# TelTail_Lights_EP_2v1.net
KiCad netlist of a schematic drawn in EAGLE
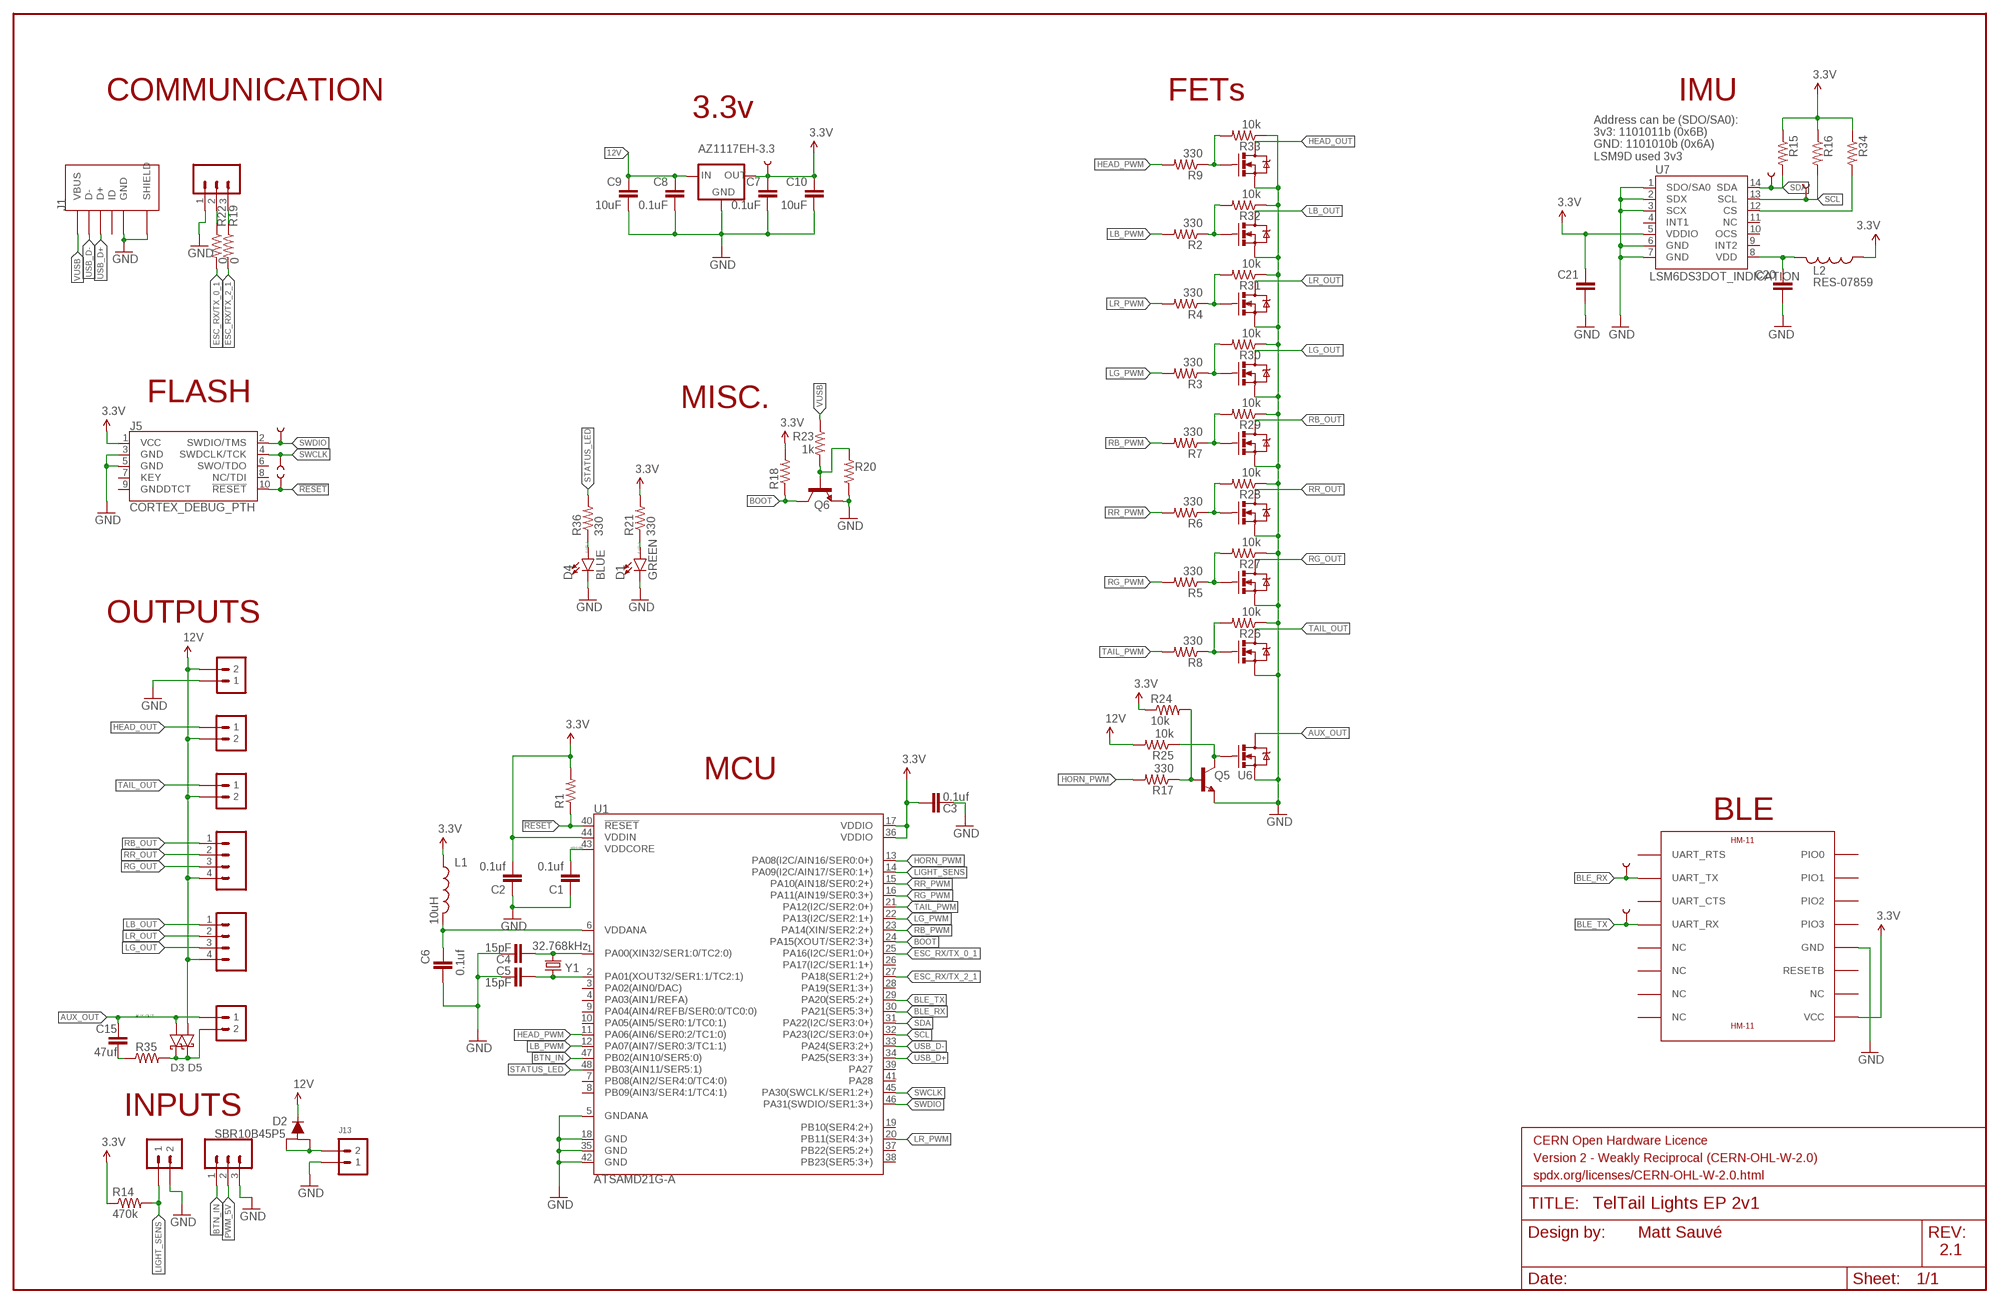
[diagram p0: schematic, sheet 1]

(export (version "E")
  (design (tool "Eeschema 10.0.6"))
  (components
    (comp (ref "C1")
      (value "0.1uf")
      (footprint "eagle-import:0603-CAP")
      (libsource (lib "eagle-import") (part "CAP0603-CAP"))
    )
    (comp (ref "C2")
      (value "0.1uf")
      (footprint "eagle-import:0603-CAP")
      (libsource (lib "eagle-import") (part "CAP0603-CAP"))
    )
    (comp (ref "C3")
      (value "0.1uf")
      (footprint "eagle-import:0603-CAP")
      (libsource (lib "eagle-import") (part "CAP0603-CAP"))
    )
    (comp (ref "C4")
      (value "15pF")
      (footprint "eagle-import:0603-CAP")
      (libsource (lib "eagle-import") (part "CAP0603-CAP"))
    )
    (comp (ref "C5")
      (value "15pF")
      (footprint "eagle-import:0603-CAP")
      (libsource (lib "eagle-import") (part "CAP0603-CAP"))
    )
    (comp (ref "C6")
      (value "0.1uf")
      (footprint "eagle-import:0603-CAP")
      (libsource (lib "eagle-import") (part "CAP0603-CAP"))
    )
    (comp (ref "C7")
      (value "0.1uF")
      (footprint "eagle-import:0603-CAP")
      (libsource (lib "eagle-import") (part "CAP0603-CAP"))
    )
    (comp (ref "C8")
      (value "0.1uF")
      (footprint "eagle-import:0603-CAP")
      (libsource (lib "eagle-import") (part "CAP0603-CAP"))
    )
    (comp (ref "C9")
      (value "10uF")
      (footprint "eagle-import:0603-CAP")
      (libsource (lib "eagle-import") (part "CAP0603-CAP"))
    )
    (comp (ref "C10")
      (value "10uF")
      (footprint "eagle-import:0603-CAP")
      (libsource (lib "eagle-import") (part "CAP0603-CAP"))
    )
    (comp (ref "C15")
      (value "47uf")
      (footprint "eagle-import:1210-CAP")
      (libsource (lib "eagle-import") (part "CAP1210"))
    )
    (comp (ref "C20")
      (value "0.1uF")
      (footprint "eagle-import:0603-CAP")
      (libsource (lib "eagle-import") (part "CAP0603-CAP"))
    )
    (comp (ref "C21")
      (value "0.1uF")
      (footprint "eagle-import:0603-CAP")
      (libsource (lib "eagle-import") (part "CAP0603-CAP"))
    )
    (comp (ref "D1")
      (value "GREEN")
      (footprint "eagle-import:LED-0603-2")
      (libsource (lib "eagle-import") (part "LED0603"))
    )
    (comp (ref "D2")
      (value "SBR10B45P5")
      (footprint "eagle-import:POWERDI5")
      (libsource (lib "eagle-import") (part "SBR10B45P5"))
    )
    (comp (ref "D3")
      (value "PMEG2010ER")
      (footprint "eagle-import:SOD-123W")
      (libsource (lib "eagle-import") (part "PMEG2010ER"))
    )
    (comp (ref "D4")
      (value "BLUE")
      (footprint "eagle-import:LED-0603-2")
      (libsource (lib "eagle-import") (part "LED0603"))
    )
    (comp (ref "D5")
      (value "PMEG2010ER")
      (footprint "eagle-import:SOD-123W")
      (libsource (lib "eagle-import") (part "PMEG2010ER"))
    )
    (comp (ref "FRAME1")
      (value "FRAME-LEDGER_CERN_WEAK")
      (footprint "eagle-import:CERN_WEAK")
      (libsource (lib "eagle-import") (part "FRAME-LEDGER_CERN_WEAK"))
    )
    (comp (ref "J1")
      (value "USB3160-XX-XXXX-X-X_REVA")
      (footprint "eagle-import:GCT_USB3160-XX-XXXX-X-X_REVA")
      (fields (field (name "MF") "Global Connector Technology") (field (name "MP") "USB3160-30-0170-0-C"))
      (libsource (lib "eagle-import") (part "USB3160-XX-XXXX-X-X_REVA"))
    )
    (comp (ref "J3")
      (value "JST_PH_3POS")
      (footprint "eagle-import:JST_PH_3POS")
      (libsource (lib "eagle-import") (part "JST_PH_3POS"))
    )
    (comp (ref "J4")
      (value "JST_PH_2POS")
      (footprint "eagle-import:JST_PH_2POS")
      (libsource (lib "eagle-import") (part "JST_PH_2POS"))
    )
    (comp (ref "J5")
      (value "CORTEX_DEBUG_PTH")
      (footprint "eagle-import:2X5-PTH-1.27MM-2")
      (libsource (lib "eagle-import") (part "CORTEX_DEBUG_PTH"))
    )
    (comp (ref "J6")
      (value "JST_PH_2POS")
      (footprint "eagle-import:JST_PH_2POS")
      (libsource (lib "eagle-import") (part "JST_PH_2POS"))
    )
    (comp (ref "J7")
      (value "JST_PH_2POS")
      (footprint "eagle-import:JST_PH_2POS")
      (libsource (lib "eagle-import") (part "JST_PH_2POS"))
    )
    (comp (ref "J8")
      (value "JST_PH_4POS")
      (footprint "eagle-import:JST_PH_4POS")
      (libsource (lib "eagle-import") (part "JST_PH_4POS"))
    )
    (comp (ref "J9")
      (value "JST_PH_4POS")
      (footprint "eagle-import:JST_PH_4POS")
      (libsource (lib "eagle-import") (part "JST_PH_4POS"))
    )
    (comp (ref "J10")
      (value "JST_PH_2POS")
      (footprint "eagle-import:JST_PH_2POS")
      (libsource (lib "eagle-import") (part "JST_PH_2POS"))
    )
    (comp (ref "J11")
      (value "JST_PH_2POS")
      (footprint "eagle-import:JST_PH_2POS")
      (libsource (lib "eagle-import") (part "JST_PH_2POS"))
    )
    (comp (ref "J12")
      (value "JST_PH_3POS")
      (footprint "eagle-import:JST_PH_3POS")
      (libsource (lib "eagle-import") (part "JST_PH_3POS"))
    )
    (comp (ref "J13")
      (value "TERM_BLOCK_SPRING_2POS_5MM")
      (footprint "eagle-import:TERM_BLOCK_SPRING_2POS_5MM")
      (libsource (lib "eagle-import") (part "TERM_BLOCK_SPRING_2POS_5MM"))
    )
    (comp (ref "L1")
      (value "10uH")
      (footprint "eagle-import:0603-IND")
      (libsource (lib "eagle-import") (part "INDUCTOR0603"))
    )
    (comp (ref "L2")
      (value "RES-07859")
      (footprint "eagle-import:0603-IND")
      (libsource (lib "eagle-import") (part "INDUCTOR0603"))
    )
    (comp (ref "Q1")
      (value "DUAL_NFET_3.5A")
      (footprint "eagle-import:TSOT26")
      (libsource (lib "eagle-import") (part "DUAL_NFET_3.5A"))
    )
    (comp (ref "Q2")
      (value "DUAL_NFET_3.5A")
      (footprint "eagle-import:TSOT26")
      (libsource (lib "eagle-import") (part "DUAL_NFET_3.5A"))
    )
    (comp (ref "Q3")
      (value "DUAL_NFET_3.5A")
      (footprint "eagle-import:TSOT26")
      (libsource (lib "eagle-import") (part "DUAL_NFET_3.5A"))
    )
    (comp (ref "Q4")
      (value "DUAL_NFET_3.5A")
      (footprint "eagle-import:TSOT26")
      (libsource (lib "eagle-import") (part "DUAL_NFET_3.5A"))
    )
    (comp (ref "Q5")
      (value "500mA/300V")
      (footprint "eagle-import:SOT23-3")
      (libsource (lib "eagle-import") (part "TRANS_NPN-MMBTA42"))
    )
    (comp (ref "Q6")
      (value "500mA/300V")
      (footprint "eagle-import:SOT23-3")
      (libsource (lib "eagle-import") (part "TRANS_NPN-MMBTA42"))
    )
    (comp (ref "R1")
      (value "10k")
      (footprint "eagle-import:RES-0402")
      (libsource (lib "eagle-import") (part "RES-0402"))
    )
    (comp (ref "R2")
      (value "330")
      (footprint "eagle-import:RES-0402")
      (libsource (lib "eagle-import") (part "RES-0402"))
    )
    (comp (ref "R3")
      (value "330")
      (footprint "eagle-import:RES-0402")
      (libsource (lib "eagle-import") (part "RES-0402"))
    )
    (comp (ref "R4")
      (value "330")
      (footprint "eagle-import:RES-0402")
      (libsource (lib "eagle-import") (part "RES-0402"))
    )
    (comp (ref "R5")
      (value "330")
      (footprint "eagle-import:RES-0402")
      (libsource (lib "eagle-import") (part "RES-0402"))
    )
    (comp (ref "R6")
      (value "330")
      (footprint "eagle-import:RES-0402")
      (libsource (lib "eagle-import") (part "RES-0402"))
    )
    (comp (ref "R7")
      (value "330")
      (footprint "eagle-import:RES-0402")
      (libsource (lib "eagle-import") (part "RES-0402"))
    )
    (comp (ref "R8")
      (value "330")
      (footprint "eagle-import:RES-0402")
      (libsource (lib "eagle-import") (part "RES-0402"))
    )
    (comp (ref "R9")
      (value "330")
      (footprint "eagle-import:RES-0402")
      (libsource (lib "eagle-import") (part "RES-0402"))
    )
    (comp (ref "R14")
      (value "470k")
      (footprint "eagle-import:RES-0603")
      (libsource (lib "eagle-import") (part "RES-0603"))
    )
    (comp (ref "R15")
      (value "10k")
      (footprint "eagle-import:RES-0402")
      (libsource (lib "eagle-import") (part "RES-0402"))
    )
    (comp (ref "R16")
      (value "10k")
      (footprint "eagle-import:RES-0402")
      (libsource (lib "eagle-import") (part "RES-0402"))
    )
    (comp (ref "R17")
      (value "330")
      (footprint "eagle-import:RES-0402")
      (libsource (lib "eagle-import") (part "RES-0402"))
    )
    (comp (ref "R18")
      (value "10k")
      (footprint "eagle-import:RES-0402")
      (libsource (lib "eagle-import") (part "RES-0402"))
    )
    (comp (ref "R19")
      (value "0")
      (footprint "eagle-import:RES-0603")
      (libsource (lib "eagle-import") (part "RES-0603"))
    )
    (comp (ref "R20")
      (value "10k")
      (footprint "eagle-import:RES-0402")
      (libsource (lib "eagle-import") (part "RES-0402"))
    )
    (comp (ref "R21")
      (value "330")
      (footprint "eagle-import:RES-0402")
      (libsource (lib "eagle-import") (part "RES-0402"))
    )
    (comp (ref "R22")
      (value "0")
      (footprint "eagle-import:RES-0603")
      (libsource (lib "eagle-import") (part "RES-0603"))
    )
    (comp (ref "R23")
      (value "1k")
      (footprint "eagle-import:RES-0402")
      (libsource (lib "eagle-import") (part "RES-0402"))
    )
    (comp (ref "R24")
      (value "10k")
      (footprint "eagle-import:RES-0402")
      (libsource (lib "eagle-import") (part "RES-0402"))
    )
    (comp (ref "R25")
      (value "10k")
      (footprint "eagle-import:RES-0402")
      (libsource (lib "eagle-import") (part "RES-0402"))
    )
    (comp (ref "R26")
      (value "10k")
      (footprint "eagle-import:RES-0402")
      (libsource (lib "eagle-import") (part "RES-0402"))
    )
    (comp (ref "R27")
      (value "10k")
      (footprint "eagle-import:RES-0402")
      (libsource (lib "eagle-import") (part "RES-0402"))
    )
    (comp (ref "R28")
      (value "10k")
      (footprint "eagle-import:RES-0402")
      (libsource (lib "eagle-import") (part "RES-0402"))
    )
    (comp (ref "R29")
      (value "10k")
      (footprint "eagle-import:RES-0402")
      (libsource (lib "eagle-import") (part "RES-0402"))
    )
    (comp (ref "R30")
      (value "10k")
      (footprint "eagle-import:RES-0402")
      (libsource (lib "eagle-import") (part "RES-0402"))
    )
    (comp (ref "R31")
      (value "10k")
      (footprint "eagle-import:RES-0402")
      (libsource (lib "eagle-import") (part "RES-0402"))
    )
    (comp (ref "R32")
      (value "10k")
      (footprint "eagle-import:RES-0402")
      (libsource (lib "eagle-import") (part "RES-0402"))
    )
    (comp (ref "R33")
      (value "10k")
      (footprint "eagle-import:RES-0402")
      (libsource (lib "eagle-import") (part "RES-0402"))
    )
    (comp (ref "R34")
      (value "10k")
      (footprint "eagle-import:RES-0402")
      (libsource (lib "eagle-import") (part "RES-0402"))
    )
    (comp (ref "R35")
      (value "100")
      (footprint "eagle-import:0805-RES")
      (libsource (lib "eagle-import") (part "RESISTOR0805"))
    )
    (comp (ref "R36")
      (value "330")
      (footprint "eagle-import:RES-0402")
      (libsource (lib "eagle-import") (part "RES-0402"))
    )
    (comp (ref "TP1")
      (value "1MM_TP")
      (footprint "eagle-import:1MM_TP")
      (libsource (lib "eagle-import") (part "1MM_TP"))
    )
    (comp (ref "TP2")
      (value "1MM_TP")
      (footprint "eagle-import:1MM_TP")
      (libsource (lib "eagle-import") (part "1MM_TP"))
    )
    (comp (ref "TP3")
      (value "1MM_TP")
      (footprint "eagle-import:1MM_TP")
      (libsource (lib "eagle-import") (part "1MM_TP"))
    )
    (comp (ref "TP4")
      (value "1MM_TP")
      (footprint "eagle-import:1MM_TP")
      (libsource (lib "eagle-import") (part "1MM_TP"))
    )
    (comp (ref "TP5")
      (value "1MM_TP")
      (footprint "eagle-import:1MM_TP")
      (libsource (lib "eagle-import") (part "1MM_TP"))
    )
    (comp (ref "TP8")
      (value "1MM_TP")
      (footprint "eagle-import:1MM_TP")
      (libsource (lib "eagle-import") (part "1MM_TP"))
    )
    (comp (ref "TP9")
      (value "1MM_TP")
      (footprint "eagle-import:1MM_TP")
      (libsource (lib "eagle-import") (part "1MM_TP"))
    )
    (comp (ref "TP10")
      (value "1MM_TP")
      (footprint "eagle-import:1MM_TP")
      (libsource (lib "eagle-import") (part "1MM_TP"))
    )
    (comp (ref "U1")
      (value "ATSAMD21G-A")
      (footprint "eagle-import:TQFP-48")
      (libsource (lib "eagle-import") (part "ATSAMD21G-A"))
    )
    (comp (ref "U3")
      (value "HM-11")
      (footprint "eagle-import:HM-11")
      (libsource (lib "eagle-import") (part "HM-11"))
    )
    (comp (ref "U4")
      (value "AZ1117EH-3.3")
      (footprint "eagle-import:SOT-223")
      (libsource (lib "eagle-import") (part "AZ1117EH-3.3"))
    )
    (comp (ref "U6")
      (value "PSMN8R5-60YS")
      (footprint "eagle-import:SOT669")
      (libsource (lib "eagle-import") (part "PSMN8R5-60YS"))
    )
    (comp (ref "U7")
      (value "LSM6DS3DOT_INDICATION")
      (footprint "eagle-import:LGA14L_DOT_INDICATOR")
      (libsource (lib "eagle-import") (part "LSM6DS3DOT_INDICATION"))
    )
    (comp (ref "Y1")
      (value "32.768kHz")
      (footprint "eagle-import:CRYSTAL-SMD-3.2X1.5MM")
      (libsource (lib "eagle-import") (part "CRYSTAL-32.768KHZSMD-3.2X1.5"))
    )
  )
  (nets
    (net (code "1") (name "/P_LED_0") (class "Default")
      (node (ref "D1") (pin "A") (pinfunction "A_A") (pintype "passive"))
      (node (ref "R21") (pin "1") (pinfunction "1_1") (pintype "passive"))
    )
    (net (code "2") (name "/S_LED_0") (class "Default")
      (node (ref "D4") (pin "A") (pinfunction "A_A") (pintype "passive"))
      (node (ref "R36") (pin "1") (pinfunction "1_1") (pintype "passive"))
    )
    (net (code "3") (name "/VDDCORE") (class "Default")
      (node (ref "C1") (pin "2") (pinfunction "2_2") (pintype "passive"))
      (node (ref "U1") (pin "43") (pinfunction "VDDCORE_43") (pintype "bidirectional"))
    )
    (net (code "4") (name "/~{RESET}") (class "Default")
      (node (ref "J5") (pin "10") (pinfunction "~{RESET}_10") (pintype "bidirectional"))
      (node (ref "R1") (pin "1") (pinfunction "1_1") (pintype "passive"))
      (node (ref "TP10") (pin "P$1") (pinfunction "1_P$1") (pintype "bidirectional"))
      (node (ref "U1") (pin "40") (pinfunction "~{RESET}_40") (pintype "bidirectional"))
    )
    (net (code "5") (name "3.3V") (class "Default")
      (node (ref "C10") (pin "1") (pinfunction "1_1") (pintype "passive"))
      (node (ref "C2") (pin "2") (pinfunction "2_2") (pintype "passive"))
      (node (ref "C21") (pin "1") (pinfunction "1_1") (pintype "passive"))
      (node (ref "C3") (pin "2") (pinfunction "2_2") (pintype "passive"))
      (node (ref "C7") (pin "1") (pinfunction "1_1") (pintype "passive"))
      (node (ref "J5") (pin "1") (pinfunction "VCC_1") (pintype "bidirectional"))
      (node (ref "L1") (pin "1") (pinfunction "1_1") (pintype "passive"))
      (node (ref "L2") (pin "1") (pinfunction "1_1") (pintype "passive"))
      (node (ref "R1") (pin "2") (pinfunction "2_2") (pintype "passive"))
      (node (ref "R14") (pin "1") (pinfunction "1_1") (pintype "passive"))
      (node (ref "R15") (pin "1") (pinfunction "1_1") (pintype "passive"))
      (node (ref "R16") (pin "1") (pinfunction "1_1") (pintype "passive"))
      (node (ref "R18") (pin "2") (pinfunction "2_2") (pintype "passive"))
      (node (ref "R21") (pin "2") (pinfunction "2_2") (pintype "passive"))
      (node (ref "R24") (pin "1") (pinfunction "1_1") (pintype "passive"))
      (node (ref "R34") (pin "1") (pinfunction "1_1") (pintype "passive"))
      (node (ref "TP3") (pin "P$1") (pinfunction "1_P$1") (pintype "bidirectional"))
      (node (ref "U1") (pin "17") (pinfunction "VDDIO_17") (pintype "bidirectional"))
      (node (ref "U1") (pin "36") (pinfunction "VDDIO_36") (pintype "bidirectional"))
      (node (ref "U1") (pin "44") (pinfunction "VDDIN_44") (pintype "bidirectional"))
      (node (ref "U3") (pin "VCC") (pinfunction "VCC_VCC") (pintype "bidirectional"))
      (node (ref "U4") (pin "2") (pinfunction "OUT_2") (pintype "passive"))
      (node (ref "U4") (pin "4") (pinfunction "OUT_4") (pintype "passive"))
      (node (ref "U7") (pin "5") (pinfunction "VDDIO_5") (pintype "bidirectional"))
    )
    (net (code "6") (name "12V") (class "Default")
      (node (ref "C8") (pin "1") (pinfunction "1_1") (pintype "passive"))
      (node (ref "C9") (pin "1") (pinfunction "1_1") (pintype "passive"))
      (node (ref "D2") (pin "CATHODE") (pinfunction "C_CATHODE") (pintype "passive"))
      (node (ref "D5") (pin "2") (pinfunction "ANODE_2") (pintype "bidirectional"))
      (node (ref "J4") (pin "2") (pinfunction "2_2") (pintype "passive"))
      (node (ref "J6") (pin "2") (pinfunction "2_2") (pintype "passive"))
      (node (ref "J7") (pin "2") (pinfunction "2_2") (pintype "passive"))
      (node (ref "J8") (pin "4") (pinfunction "4_4") (pintype "passive"))
      (node (ref "J9") (pin "4") (pinfunction "4_4") (pintype "passive"))
      (node (ref "R25") (pin "2") (pinfunction "2_2") (pintype "passive"))
      (node (ref "U4") (pin "3") (pinfunction "IN_3") (pintype "input"))
    )
    (net (code "7") (name "AUX_OUT") (class "Default")
      (node (ref "C15") (pin "1") (pinfunction "1_1") (pintype "passive"))
      (node (ref "D3") (pin "2") (pinfunction "ANODE_2") (pintype "bidirectional"))
      (node (ref "J10") (pin "1") (pinfunction "1_1") (pintype "passive"))
      (node (ref "U6") (pin "P$1") (pinfunction "D_P$1") (pintype "passive"))
      (node (ref "U6") (pin "P$2") (pinfunction "D_P$2") (pintype "passive"))
    )
    (net (code "8") (name "BLE_RX") (class "Default")
      (node (ref "TP2") (pin "P$1") (pinfunction "1_P$1") (pintype "bidirectional"))
      (node (ref "U1") (pin "30") (pinfunction "PA21(SER5:3+)_30") (pintype "bidirectional"))
      (node (ref "U3") (pin "UART_TX") (pinfunction "UART_TX_UART_TX") (pintype "bidirectional"))
    )
    (net (code "9") (name "BLE_TX") (class "Default")
      (node (ref "TP1") (pin "P$1") (pinfunction "1_P$1") (pintype "bidirectional"))
      (node (ref "U1") (pin "29") (pinfunction "PA20(SER5:2+)_29") (pintype "bidirectional"))
      (node (ref "U3") (pin "UART_RX") (pinfunction "UART_RX_UART_RX") (pintype "bidirectional"))
    )
    (net (code "10") (name "BOOT") (class "Default")
      (node (ref "Q6") (pin "3") (pinfunction "C_3") (pintype "passive"))
      (node (ref "R18") (pin "1") (pinfunction "1_1") (pintype "passive"))
      (node (ref "U1") (pin "24") (pinfunction "PA15(XOUT/SER2:3+)_24") (pintype "bidirectional"))
    )
    (net (code "11") (name "BTN_IN") (class "Default")
      (node (ref "J12") (pin "1") (pinfunction "2_1") (pintype "passive"))
      (node (ref "U1") (pin "47") (pinfunction "PB02(AIN10/SER5:0)_47") (pintype "bidirectional"))
    )
    (net (code "12") (name "ESC_RX{slash}TX_0_1") (class "Default")
      (node (ref "R22") (pin "2") (pinfunction "2_2") (pintype "passive"))
      (node (ref "U1") (pin "25") (pinfunction "PA16(I2C/SER1:0+)_25") (pintype "bidirectional"))
    )
    (net (code "13") (name "ESC_RX{slash}TX_2_1") (class "Default")
      (node (ref "R19") (pin "2") (pinfunction "2_2") (pintype "passive"))
      (node (ref "U1") (pin "27") (pinfunction "PA18(SER1:2+)_27") (pintype "bidirectional"))
    )
    (net (code "14") (name "GND") (class "Default")
      (node (ref "C1") (pin "1") (pinfunction "1_1") (pintype "passive"))
      (node (ref "C10") (pin "2") (pinfunction "2_2") (pintype "passive"))
      (node (ref "C2") (pin "1") (pinfunction "1_1") (pintype "passive"))
      (node (ref "C20") (pin "2") (pinfunction "2_2") (pintype "passive"))
      (node (ref "C21") (pin "2") (pinfunction "2_2") (pintype "passive"))
      (node (ref "C3") (pin "1") (pinfunction "1_1") (pintype "passive"))
      (node (ref "C4") (pin "2") (pinfunction "2_2") (pintype "passive"))
      (node (ref "C5") (pin "2") (pinfunction "2_2") (pintype "passive"))
      (node (ref "C6") (pin "2") (pinfunction "2_2") (pintype "passive"))
      (node (ref "C7") (pin "2") (pinfunction "2_2") (pintype "passive"))
      (node (ref "C8") (pin "2") (pinfunction "2_2") (pintype "passive"))
      (node (ref "C9") (pin "2") (pinfunction "2_2") (pintype "passive"))
      (node (ref "D1") (pin "C") (pinfunction "C_C") (pintype "passive"))
      (node (ref "D4") (pin "C") (pinfunction "C_C") (pintype "passive"))
      (node (ref "J1") (pin "5") (pinfunction "GND_5") (pintype "power_in"))
      (node (ref "J1") (pin "6") (pinfunction "SHIELD_6") (pintype "passive"))
      (node (ref "J1") (pin "7") (pinfunction "SHIELD_7") (pintype "passive"))
      (node (ref "J1") (pin "8") (pinfunction "SHIELD_8") (pintype "passive"))
      (node (ref "J11") (pin "2") (pinfunction "2_2") (pintype "passive"))
      (node (ref "J12") (pin "3") (pinfunction "4_3") (pintype "passive"))
      (node (ref "J13") (pin "P1_1") (pinfunction "1_P1_1") (pintype "passive"))
      (node (ref "J13") (pin "P1_2") (pinfunction "1_P1_2") (pintype "passive"))
      (node (ref "J3") (pin "1") (pinfunction "2_1") (pintype "passive"))
      (node (ref "J4") (pin "1") (pinfunction "1_1") (pintype "passive"))
      (node (ref "J5") (pin "3") (pinfunction "GND_3") (pintype "bidirectional"))
      (node (ref "J5") (pin "5") (pinfunction "GND_5") (pintype "bidirectional"))
      (node (ref "Q1") (pin "2") (pinfunction "S_2") (pintype "passive"))
      (node (ref "Q1") (pin "5") (pinfunction "S_5") (pintype "passive"))
      (node (ref "Q2") (pin "2") (pinfunction "S_2") (pintype "passive"))
      (node (ref "Q2") (pin "5") (pinfunction "S_5") (pintype "passive"))
      (node (ref "Q3") (pin "2") (pinfunction "S_2") (pintype "passive"))
      (node (ref "Q3") (pin "5") (pinfunction "S_5") (pintype "passive"))
      (node (ref "Q4") (pin "2") (pinfunction "S_2") (pintype "passive"))
      (node (ref "Q4") (pin "5") (pinfunction "S_5") (pintype "passive"))
      (node (ref "Q5") (pin "2") (pinfunction "E_2") (pintype "passive"))
      (node (ref "Q6") (pin "2") (pinfunction "E_2") (pintype "passive"))
      (node (ref "R20") (pin "1") (pinfunction "1_1") (pintype "passive"))
      (node (ref "R26") (pin "1") (pinfunction "1_1") (pintype "passive"))
      (node (ref "R27") (pin "1") (pinfunction "1_1") (pintype "passive"))
      (node (ref "R28") (pin "1") (pinfunction "1_1") (pintype "passive"))
      (node (ref "R29") (pin "1") (pinfunction "1_1") (pintype "passive"))
      (node (ref "R30") (pin "1") (pinfunction "1_1") (pintype "passive"))
      (node (ref "R31") (pin "1") (pinfunction "1_1") (pintype "passive"))
      (node (ref "R32") (pin "1") (pinfunction "1_1") (pintype "passive"))
      (node (ref "R33") (pin "1") (pinfunction "1_1") (pintype "passive"))
      (node (ref "U1") (pin "18") (pinfunction "GND_18") (pintype "bidirectional"))
      (node (ref "U1") (pin "35") (pinfunction "GND_35") (pintype "bidirectional"))
      (node (ref "U1") (pin "42") (pinfunction "GND_42") (pintype "bidirectional"))
      (node (ref "U1") (pin "5") (pinfunction "GNDANA_5") (pintype "bidirectional"))
      (node (ref "U3") (pin "GND") (pinfunction "GND_GND") (pintype "bidirectional"))
      (node (ref "U4") (pin "1") (pinfunction "GND_1") (pintype "input"))
      (node (ref "U6") (pin "1") (pinfunction "S_1") (pintype "passive"))
      (node (ref "U6") (pin "2") (pinfunction "S_2") (pintype "passive"))
      (node (ref "U6") (pin "3") (pinfunction "S_3") (pintype "passive"))
      (node (ref "U7") (pin "1") (pinfunction "SDO/SA0_1") (pintype "bidirectional"))
      (node (ref "U7") (pin "2") (pinfunction "SDX_2") (pintype "bidirectional"))
      (node (ref "U7") (pin "3") (pinfunction "SCX_3") (pintype "bidirectional"))
      (node (ref "U7") (pin "6") (pinfunction "GND_6") (pintype "bidirectional"))
      (node (ref "U7") (pin "7") (pinfunction "GND_7") (pintype "bidirectional"))
    )
    (net (code "15") (name "HEAD_OUT") (class "Default")
      (node (ref "J6") (pin "1") (pinfunction "1_1") (pintype "passive"))
      (node (ref "Q1") (pin "4") (pinfunction "D_4") (pintype "passive"))
    )
    (net (code "16") (name "HEAD_PWM") (class "Default")
      (node (ref "R9") (pin "2") (pinfunction "2_2") (pintype "passive"))
      (node (ref "U1") (pin "11") (pinfunction "PA06(AIN6/SER0:2/TC1:0)_11") (pintype "bidirectional"))
    )
    (net (code "17") (name "HORN_PWM") (class "Default")
      (node (ref "R17") (pin "2") (pinfunction "2_2") (pintype "passive"))
      (node (ref "U1") (pin "13") (pinfunction "PA08(I2C/AIN16/SER0:0+)_13") (pintype "bidirectional"))
    )
    (net (code "18") (name "LB_OUT") (class "Default")
      (node (ref "J9") (pin "1") (pinfunction "1_1") (pintype "passive"))
      (node (ref "Q1") (pin "6") (pinfunction "D_6") (pintype "passive"))
    )
    (net (code "19") (name "LB_PWM") (class "Default")
      (node (ref "R2") (pin "2") (pinfunction "2_2") (pintype "passive"))
      (node (ref "U1") (pin "12") (pinfunction "PA07(AIN7/SER0:3/TC1:1)_12") (pintype "bidirectional"))
    )
    (net (code "20") (name "LG_OUT") (class "Default")
      (node (ref "J9") (pin "3") (pinfunction "3_3") (pintype "passive"))
      (node (ref "Q2") (pin "6") (pinfunction "D_6") (pintype "passive"))
    )
    (net (code "21") (name "LG_PWM") (class "Default")
      (node (ref "R3") (pin "2") (pinfunction "2_2") (pintype "passive"))
      (node (ref "U1") (pin "22") (pinfunction "PA13(I2C/SER2:1+)_22") (pintype "bidirectional"))
    )
    (net (code "22") (name "LIGHT_SENS") (class "Default")
      (node (ref "J11") (pin "1") (pinfunction "1_1") (pintype "passive"))
      (node (ref "R14") (pin "2") (pinfunction "2_2") (pintype "passive"))
      (node (ref "U1") (pin "14") (pinfunction "PA09(I2C/AIN17/SER0:1+)_14") (pintype "bidirectional"))
    )
    (net (code "23") (name "LR_OUT") (class "Default")
      (node (ref "J9") (pin "2") (pinfunction "2_2") (pintype "passive"))
      (node (ref "Q2") (pin "4") (pinfunction "D_4") (pintype "passive"))
    )
    (net (code "24") (name "LR_PWM") (class "Default")
      (node (ref "R4") (pin "2") (pinfunction "2_2") (pintype "passive"))
      (node (ref "U1") (pin "20") (pinfunction "PB11(SER4:3+)_20") (pintype "bidirectional"))
    )
    (net (code "25") (name "Net-(C15-Pad2)") (class "Default")
      (node (ref "C15") (pin "2") (pinfunction "2_2") (pintype "passive"))
      (node (ref "R35") (pin "1") (pinfunction "1_1") (pintype "passive"))
    )
    (net (code "26") (name "Net-(D2-A)") (class "Default")
      (node (ref "D2") (pin "ANODE1") (pinfunction "A_ANODE1") (pintype "passive"))
      (node (ref "D2") (pin "ANODE2") (pinfunction "A1_ANODE2") (pintype "passive"))
      (node (ref "J13") (pin "P2_1") (pinfunction "2_P2_1") (pintype "passive"))
      (node (ref "J13") (pin "P2_2") (pinfunction "2_P2_2") (pintype "passive"))
    )
    (net (code "27") (name "Net-(D3-CATHODE)") (class "Default")
      (node (ref "D3") (pin "1") (pinfunction "CATHODE_1") (pintype "bidirectional"))
      (node (ref "D5") (pin "1") (pinfunction "CATHODE_1") (pintype "bidirectional"))
      (node (ref "J10") (pin "2") (pinfunction "2_2") (pintype "passive"))
      (node (ref "R35") (pin "2") (pinfunction "2_2") (pintype "passive"))
    )
    (net (code "28") (name "Net-(J3-3)") (class "Default")
      (node (ref "J3") (pin "2") (pinfunction "3_2") (pintype "passive"))
      (node (ref "R22") (pin "1") (pinfunction "1_1") (pintype "passive"))
    )
    (net (code "29") (name "Net-(J3-4)") (class "Default")
      (node (ref "J3") (pin "3") (pinfunction "4_3") (pintype "passive"))
      (node (ref "R19") (pin "1") (pinfunction "1_1") (pintype "passive"))
    )
    (net (code "30") (name "Net-(Q1A-G)") (class "Default")
      (node (ref "Q1") (pin "1") (pinfunction "G_1") (pintype "passive"))
      (node (ref "R2") (pin "1") (pinfunction "1_1") (pintype "passive"))
      (node (ref "R32") (pin "2") (pinfunction "2_2") (pintype "passive"))
    )
    (net (code "31") (name "Net-(Q1B-G)") (class "Default")
      (node (ref "Q1") (pin "3") (pinfunction "G_3") (pintype "passive"))
      (node (ref "R33") (pin "2") (pinfunction "2_2") (pintype "passive"))
      (node (ref "R9") (pin "1") (pinfunction "1_1") (pintype "passive"))
    )
    (net (code "32") (name "Net-(Q2A-G)") (class "Default")
      (node (ref "Q2") (pin "1") (pinfunction "G_1") (pintype "passive"))
      (node (ref "R3") (pin "1") (pinfunction "1_1") (pintype "passive"))
      (node (ref "R30") (pin "2") (pinfunction "2_2") (pintype "passive"))
    )
    (net (code "33") (name "Net-(Q2B-G)") (class "Default")
      (node (ref "Q2") (pin "3") (pinfunction "G_3") (pintype "passive"))
      (node (ref "R31") (pin "2") (pinfunction "2_2") (pintype "passive"))
      (node (ref "R4") (pin "1") (pinfunction "1_1") (pintype "passive"))
    )
    (net (code "34") (name "Net-(Q3A-G)") (class "Default")
      (node (ref "Q3") (pin "1") (pinfunction "G_1") (pintype "passive"))
      (node (ref "R28") (pin "2") (pinfunction "2_2") (pintype "passive"))
      (node (ref "R6") (pin "1") (pinfunction "1_1") (pintype "passive"))
    )
    (net (code "35") (name "Net-(Q3B-G)") (class "Default")
      (node (ref "Q3") (pin "3") (pinfunction "G_3") (pintype "passive"))
      (node (ref "R29") (pin "2") (pinfunction "2_2") (pintype "passive"))
      (node (ref "R7") (pin "1") (pinfunction "1_1") (pintype "passive"))
    )
    (net (code "36") (name "Net-(Q4A-G)") (class "Default")
      (node (ref "Q4") (pin "1") (pinfunction "G_1") (pintype "passive"))
      (node (ref "R26") (pin "2") (pinfunction "2_2") (pintype "passive"))
      (node (ref "R8") (pin "1") (pinfunction "1_1") (pintype "passive"))
    )
    (net (code "37") (name "Net-(Q4B-G)") (class "Default")
      (node (ref "Q4") (pin "3") (pinfunction "G_3") (pintype "passive"))
      (node (ref "R27") (pin "2") (pinfunction "2_2") (pintype "passive"))
      (node (ref "R5") (pin "1") (pinfunction "1_1") (pintype "passive"))
    )
    (net (code "38") (name "Net-(Q5-B)") (class "Default")
      (node (ref "Q5") (pin "1") (pinfunction "B_1") (pintype "passive"))
      (node (ref "R17") (pin "1") (pinfunction "1_1") (pintype "passive"))
      (node (ref "R24") (pin "2") (pinfunction "2_2") (pintype "passive"))
    )
    (net (code "39") (name "Net-(Q5-C)") (class "Default")
      (node (ref "Q5") (pin "3") (pinfunction "C_3") (pintype "passive"))
      (node (ref "R25") (pin "1") (pinfunction "1_1") (pintype "passive"))
      (node (ref "U6") (pin "4") (pinfunction "G_4") (pintype "passive"))
    )
    (net (code "40") (name "Net-(Q6-B)") (class "Default")
      (node (ref "Q6") (pin "1") (pinfunction "B_1") (pintype "passive"))
      (node (ref "R20") (pin "2") (pinfunction "2_2") (pintype "passive"))
      (node (ref "R23") (pin "2") (pinfunction "2_2") (pintype "passive"))
    )
    (net (code "41") (name "Net-(U1-PA00(XIN32{slash}SER1:0{slash}TC2:0))") (class "Default")
      (node (ref "C4") (pin "1") (pinfunction "1_1") (pintype "passive"))
      (node (ref "U1") (pin "1") (pinfunction "PA00(XIN32/SER1:0/TC2:0)_1") (pintype "bidirectional"))
      (node (ref "Y1") (pin "P$2") (pinfunction "2_P$2") (pintype "passive"))
    )
    (net (code "42") (name "Net-(U1-PA01(XOUT32{slash}SER1:1{slash}TC2:1))") (class "Default")
      (node (ref "C5") (pin "1") (pinfunction "1_1") (pintype "passive"))
      (node (ref "U1") (pin "2") (pinfunction "PA01(XOUT32/SER1:1/TC2:1)_2") (pintype "bidirectional"))
      (node (ref "Y1") (pin "P$1") (pinfunction "1_P$1") (pintype "passive"))
    )
    (net (code "43") (name "Net-(U1-VDDANA)") (class "Default")
      (node (ref "C6") (pin "1") (pinfunction "1_1") (pintype "passive"))
      (node (ref "L1") (pin "2") (pinfunction "2_2") (pintype "passive"))
      (node (ref "U1") (pin "6") (pinfunction "VDDANA_6") (pintype "bidirectional"))
    )
    (net (code "44") (name "Net-(U7-CS)") (class "Default")
      (node (ref "R34") (pin "2") (pinfunction "2_2") (pintype "passive"))
      (node (ref "U7") (pin "12") (pinfunction "CS_12") (pintype "bidirectional"))
    )
    (net (code "45") (name "Net-(U7-VDD)") (class "Default")
      (node (ref "C20") (pin "1") (pinfunction "1_1") (pintype "passive"))
      (node (ref "L2") (pin "2") (pinfunction "2_2") (pintype "passive"))
      (node (ref "U7") (pin "8") (pinfunction "VDD_8") (pintype "bidirectional"))
    )
    (net (code "46") (name "PWM_5V") (class "Default")
      (node (ref "J12") (pin "2") (pinfunction "3_2") (pintype "passive"))
    )
    (net (code "47") (name "RB_OUT") (class "Default")
      (node (ref "J8") (pin "1") (pinfunction "1_1") (pintype "passive"))
      (node (ref "Q3") (pin "4") (pinfunction "D_4") (pintype "passive"))
    )
    (net (code "48") (name "RB_PWM") (class "Default")
      (node (ref "R7") (pin "2") (pinfunction "2_2") (pintype "passive"))
      (node (ref "U1") (pin "23") (pinfunction "PA14(XIN/SER2:2+)_23") (pintype "bidirectional"))
    )
    (net (code "49") (name "RG_OUT") (class "Default")
      (node (ref "J8") (pin "3") (pinfunction "3_3") (pintype "passive"))
      (node (ref "Q4") (pin "4") (pinfunction "D_4") (pintype "passive"))
    )
    (net (code "50") (name "RG_PWM") (class "Default")
      (node (ref "R5") (pin "2") (pinfunction "2_2") (pintype "passive"))
      (node (ref "U1") (pin "16") (pinfunction "PA11(AIN19/SER0:3+)_16") (pintype "bidirectional"))
    )
    (net (code "51") (name "RR_OUT") (class "Default")
      (node (ref "J8") (pin "2") (pinfunction "2_2") (pintype "passive"))
      (node (ref "Q3") (pin "6") (pinfunction "D_6") (pintype "passive"))
    )
    (net (code "52") (name "RR_PWM") (class "Default")
      (node (ref "R6") (pin "2") (pinfunction "2_2") (pintype "passive"))
      (node (ref "U1") (pin "15") (pinfunction "PA10(AIN18/SER0:2+)_15") (pintype "bidirectional"))
    )
    (net (code "53") (name "SCL") (class "Default")
      (node (ref "R16") (pin "2") (pinfunction "2_2") (pintype "passive"))
      (node (ref "TP5") (pin "P$1") (pinfunction "1_P$1") (pintype "bidirectional"))
      (node (ref "U1") (pin "32") (pinfunction "PA23(I2C/SER3:0+)_32") (pintype "bidirectional"))
      (node (ref "U7") (pin "13") (pinfunction "SCL_13") (pintype "bidirectional"))
    )
    (net (code "54") (name "SDA") (class "Default")
      (node (ref "R15") (pin "2") (pinfunction "2_2") (pintype "passive"))
      (node (ref "TP4") (pin "P$1") (pinfunction "1_P$1") (pintype "bidirectional"))
      (node (ref "U1") (pin "31") (pinfunction "PA22(I2C/SER3:0+)_31") (pintype "bidirectional"))
      (node (ref "U7") (pin "14") (pinfunction "SDA_14") (pintype "bidirectional"))
    )
    (net (code "55") (name "STATUS_LED") (class "Default")
      (node (ref "R36") (pin "2") (pinfunction "2_2") (pintype "passive"))
      (node (ref "U1") (pin "48") (pinfunction "PB03(AIN11/SER5:1)_48") (pintype "bidirectional"))
    )
    (net (code "56") (name "SWCLK") (class "Default")
      (node (ref "J5") (pin "4") (pinfunction "SWDCLK/TCK_4") (pintype "bidirectional"))
      (node (ref "TP9") (pin "P$1") (pinfunction "1_P$1") (pintype "bidirectional"))
      (node (ref "U1") (pin "45") (pinfunction "PA30(SWCLK/SER1:2+)_45") (pintype "bidirectional"))
    )
    (net (code "57") (name "SWDIO") (class "Default")
      (node (ref "J5") (pin "2") (pinfunction "SWDIO/TMS_2") (pintype "bidirectional"))
      (node (ref "TP8") (pin "P$1") (pinfunction "1_P$1") (pintype "bidirectional"))
      (node (ref "U1") (pin "46") (pinfunction "PA31(SWDIO/SER1:3+)_46") (pintype "bidirectional"))
    )
    (net (code "58") (name "TAIL_OUT") (class "Default")
      (node (ref "J7") (pin "1") (pinfunction "1_1") (pintype "passive"))
      (node (ref "Q4") (pin "6") (pinfunction "D_6") (pintype "passive"))
    )
    (net (code "59") (name "TAIL_PWM") (class "Default")
      (node (ref "R8") (pin "2") (pinfunction "2_2") (pintype "passive"))
      (node (ref "U1") (pin "21") (pinfunction "PA12(I2C/SER2:0+)_21") (pintype "bidirectional"))
    )
    (net (code "60") (name "USB_D+") (class "Default")
      (node (ref "J1") (pin "3") (pinfunction "D+_3") (pintype "bidirectional"))
      (node (ref "U1") (pin "34") (pinfunction "PA25(SER3:3+)_34") (pintype "bidirectional"))
    )
    (net (code "61") (name "USB_D-") (class "Default")
      (node (ref "J1") (pin "2") (pinfunction "D-_2") (pintype "bidirectional"))
      (node (ref "U1") (pin "33") (pinfunction "PA24(SER3:2+)_33") (pintype "bidirectional"))
    )
    (net (code "62") (name "VUSB") (class "Default")
      (node (ref "J1") (pin "1") (pinfunction "VBUS_1") (pintype "power_in"))
      (node (ref "R23") (pin "1") (pinfunction "1_1") (pintype "passive"))
    )
    (net (code "63") (name "unconnected-(J1-ID-Pad4)") (class "Default")
      (node (ref "J1") (pin "4") (pinfunction "ID_4") (pintype "passive"))
    )
    (net (code "64") (name "unconnected-(J5-GNDDTCT-Pad9)") (class "Default")
      (node (ref "J5") (pin "9") (pinfunction "GNDDTCT_9") (pintype "bidirectional"))
    )
    (net (code "65") (name "unconnected-(J5-KEY-Pad7)") (class "Default")
      (node (ref "J5") (pin "7") (pinfunction "KEY_7") (pintype "bidirectional"))
    )
    (net (code "66") (name "unconnected-(J5-NC{slash}TDI-Pad8)") (class "Default")
      (node (ref "J5") (pin "8") (pinfunction "NC/TDI_8") (pintype "bidirectional"))
    )
    (net (code "67") (name "unconnected-(J5-SWO{slash}TDO-Pad6)") (class "Default")
      (node (ref "J5") (pin "6") (pinfunction "SWO/TDO_6") (pintype "bidirectional"))
    )
    (net (code "68") (name "unconnected-(U1-PA02(AIN0{slash}DAC)-Pad3)") (class "Default")
      (node (ref "U1") (pin "3") (pinfunction "PA02(AIN0/DAC)_3") (pintype "bidirectional"))
    )
    (net (code "69") (name "unconnected-(U1-PA03(AIN1{slash}REFA)-Pad4)") (class "Default")
      (node (ref "U1") (pin "4") (pinfunction "PA03(AIN1/REFA)_4") (pintype "bidirectional"))
    )
    (net (code "70") (name "unconnected-(U1-PA04(AIN4{slash}REFB{slash}SER0:0{slash}TC0:0)-Pad9)") (class "Default")
      (node (ref "U1") (pin "9") (pinfunction "PA04(AIN4/REFB/SER0:0/TC0:0)_9") (pintype "bidirectional"))
    )
    (net (code "71") (name "unconnected-(U1-PA05(AIN5{slash}SER0:1{slash}TC0:1)-Pad10)") (class "Default")
      (node (ref "U1") (pin "10") (pinfunction "PA05(AIN5/SER0:1/TC0:1)_10") (pintype "bidirectional"))
    )
    (net (code "72") (name "unconnected-(U1-PA17(I2C{slash}SER1:1+)-Pad26)") (class "Default")
      (node (ref "U1") (pin "26") (pinfunction "PA17(I2C/SER1:1+)_26") (pintype "bidirectional"))
    )
    (net (code "73") (name "unconnected-(U1-PA19(SER1:3+)-Pad28)") (class "Default")
      (node (ref "U1") (pin "28") (pinfunction "PA19(SER1:3+)_28") (pintype "bidirectional"))
    )
    (net (code "74") (name "unconnected-(U1-PA27-Pad39)") (class "Default")
      (node (ref "U1") (pin "39") (pinfunction "PA27_39") (pintype "bidirectional"))
    )
    (net (code "75") (name "unconnected-(U1-PA28-Pad41)") (class "Default")
      (node (ref "U1") (pin "41") (pinfunction "PA28_41") (pintype "bidirectional"))
    )
    (net (code "76") (name "unconnected-(U1-PB08(AIN2{slash}SER4:0{slash}TC4:0)-Pad7)") (class "Default")
      (node (ref "U1") (pin "7") (pinfunction "PB08(AIN2/SER4:0/TC4:0)_7") (pintype "bidirectional"))
    )
    (net (code "77") (name "unconnected-(U1-PB09(AIN3{slash}SER4:1{slash}TC4:1)-Pad8)") (class "Default")
      (node (ref "U1") (pin "8") (pinfunction "PB09(AIN3/SER4:1/TC4:1)_8") (pintype "bidirectional"))
    )
    (net (code "78") (name "unconnected-(U1-PB10(SER4:2+)-Pad19)") (class "Default")
      (node (ref "U1") (pin "19") (pinfunction "PB10(SER4:2+)_19") (pintype "bidirectional"))
    )
    (net (code "79") (name "unconnected-(U1-PB22(SER5:2+)-Pad37)") (class "Default")
      (node (ref "U1") (pin "37") (pinfunction "PB22(SER5:2+)_37") (pintype "bidirectional"))
    )
    (net (code "80") (name "unconnected-(U1-PB23(SER5:3+)-Pad38)") (class "Default")
      (node (ref "U1") (pin "38") (pinfunction "PB23(SER5:3+)_38") (pintype "bidirectional"))
    )
    (net (code "81") (name "unconnected-(U3-NC-PadNC@5)") (class "Default")
      (node (ref "U3") (pin "NC@5") (pinfunction "NC_NC@5") (pintype "bidirectional"))
    )
    (net (code "82") (name "unconnected-(U3-NC-PadNC@6)") (class "Default")
      (node (ref "U3") (pin "NC@6") (pinfunction "NC_NC@6") (pintype "bidirectional"))
    )
    (net (code "83") (name "unconnected-(U3-NC-PadNC@7)") (class "Default")
      (node (ref "U3") (pin "NC@7") (pinfunction "NC_NC@7") (pintype "bidirectional"))
    )
    (net (code "84") (name "unconnected-(U3-NC-PadNC@8)") (class "Default")
      (node (ref "U3") (pin "NC@8") (pinfunction "NC_NC@8") (pintype "bidirectional"))
    )
    (net (code "85") (name "unconnected-(U3-NC-PadNC@10)") (class "Default")
      (node (ref "U3") (pin "NC@10") (pinfunction "NC_NC@10") (pintype "bidirectional"))
    )
    (net (code "86") (name "unconnected-(U3-PadPIO0)") (class "Default")
      (node (ref "U3") (pin "PIO0") (pinfunction "PIO0_PIO0") (pintype "bidirectional"))
    )
    (net (code "87") (name "unconnected-(U3-PadPIO1)") (class "Default")
      (node (ref "U3") (pin "PIO1") (pinfunction "PIO1_PIO1") (pintype "bidirectional"))
    )
    (net (code "88") (name "unconnected-(U3-PadPIO2)") (class "Default")
      (node (ref "U3") (pin "PIO2") (pinfunction "PIO2_PIO2") (pintype "bidirectional"))
    )
    (net (code "89") (name "unconnected-(U3-PadPIO3)") (class "Default")
      (node (ref "U3") (pin "PIO3") (pinfunction "PIO3_PIO3") (pintype "bidirectional"))
    )
    (net (code "90") (name "unconnected-(U3-PadRESETB)") (class "Default")
      (node (ref "U3") (pin "RESETB") (pinfunction "RESETB_RESETB") (pintype "bidirectional"))
    )
    (net (code "91") (name "unconnected-(U3-PadUART_CTS)") (class "Default")
      (node (ref "U3") (pin "UART_CTS") (pinfunction "UART_CTS_UART_CTS") (pintype "bidirectional"))
    )
    (net (code "92") (name "unconnected-(U3-PadUART_RTS)") (class "Default")
      (node (ref "U3") (pin "UART_RTS") (pinfunction "UART_RTS_UART_RTS") (pintype "bidirectional"))
    )
    (net (code "93") (name "unconnected-(U7-INT1-Pad4)") (class "Default")
      (node (ref "U7") (pin "4") (pinfunction "INT1_4") (pintype "bidirectional"))
    )
    (net (code "94") (name "unconnected-(U7-INT2-Pad9)") (class "Default")
      (node (ref "U7") (pin "9") (pinfunction "INT2_9") (pintype "bidirectional"))
    )
    (net (code "95") (name "unconnected-(U7-NC-Pad11)") (class "Default")
      (node (ref "U7") (pin "11") (pinfunction "NC_11") (pintype "bidirectional"))
    )
    (net (code "96") (name "unconnected-(U7-OCS-Pad10)") (class "Default")
      (node (ref "U7") (pin "10") (pinfunction "OCS_10") (pintype "bidirectional"))
    )
  )
)
